# euroWS2811.net
KiCad netlist of a schematic drawn in EAGLE
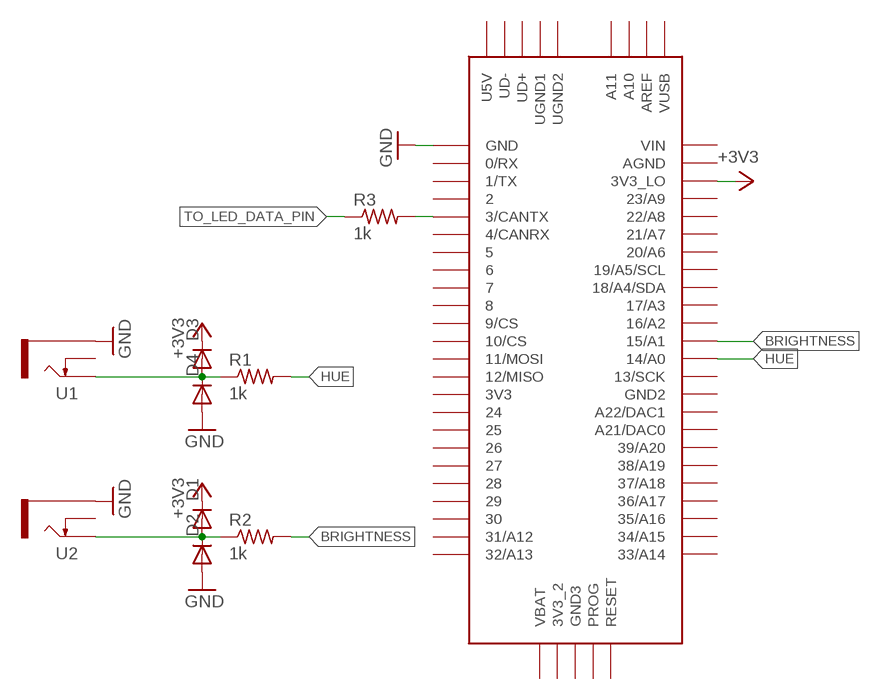
[diagram p0: schematic, sheet 1]

(export (version "E")
  (design (tool "Eeschema 10.0.6"))
  (components
    (comp (ref "D1")
      (value "SMALL_DIODEDO35-7")
      (footprint "eagle-import:DO35-7")
      (libsource (lib "eagle-import") (part "SMALL_DIODEDO35-7"))
    )
    (comp (ref "D2")
      (value "SMALL_DIODEDO35-7")
      (footprint "eagle-import:DO35-7")
      (libsource (lib "eagle-import") (part "SMALL_DIODEDO35-7"))
    )
    (comp (ref "D3")
      (value "SMALL_DIODEDO35-7")
      (footprint "eagle-import:DO35-7")
      (libsource (lib "eagle-import") (part "SMALL_DIODEDO35-7"))
    )
    (comp (ref "D4")
      (value "SMALL_DIODEDO35-7")
      (footprint "eagle-import:DO35-7")
      (libsource (lib "eagle-import") (part "SMALL_DIODEDO35-7"))
    )
    (comp (ref "R1")
      (value "1k")
      (footprint "eagle-import:0207_10")
      (libsource (lib "eagle-import") (part "R-US_0207/10"))
    )
    (comp (ref "R2")
      (value "1k")
      (footprint "eagle-import:0207_10")
      (libsource (lib "eagle-import") (part "R-US_0207/10"))
    )
    (comp (ref "R3")
      (value "1k")
      (footprint "eagle-import:0207_10")
      (libsource (lib "eagle-import") (part "R-US_0207/10"))
    )
    (comp (ref "U$1")
      (value "TEENSY_3.5/3.6")
      (footprint "eagle-import:TEENSY_3.5_3.6")
      (libsource (lib "eagle-import") (part "TEENSY_3.5/3.6"))
    )
    (comp (ref "U1")
      (value "THONKICONNNEW")
      (footprint "eagle-import:WQP-PJ301M-12_JACK")
      (libsource (lib "eagle-import") (part "THONKICONNNEW"))
    )
    (comp (ref "U2")
      (value "THONKICONNNEW")
      (footprint "eagle-import:WQP-PJ301M-12_JACK")
      (libsource (lib "eagle-import") (part "THONKICONNNEW"))
    )
  )
  (nets
    (net (code "1") (name "+3V3") (class "Default")
      (node (ref "D1") (pin "C") (pinfunction "C_C") (pintype "passive"))
      (node (ref "D3") (pin "C") (pinfunction "C_C") (pintype "passive"))
      (node (ref "U$1") (pin "3V3_LO") (pinfunction "3V3_LO_3V3_LO") (pintype "bidirectional"))
    )
    (net (code "2") (name "BRIGHTNESS") (class "Default")
      (node (ref "R2") (pin "2") (pinfunction "2_2") (pintype "passive"))
      (node (ref "U$1") (pin "15/A1") (pinfunction "15/A1_15/A1") (pintype "bidirectional"))
    )
    (net (code "3") (name "GND") (class "Default")
      (node (ref "D2") (pin "A") (pinfunction "A_A") (pintype "passive"))
      (node (ref "D4") (pin "A") (pinfunction "A_A") (pintype "passive"))
      (node (ref "U$1") (pin "GND") (pinfunction "GND_GND") (pintype "bidirectional"))
      (node (ref "U1") (pin "P$3_SLEEVE") (pinfunction "SLEEVE_P$3_SLEEVE") (pintype "passive"))
      (node (ref "U2") (pin "P$3_SLEEVE") (pinfunction "SLEEVE_P$3_SLEEVE") (pintype "passive"))
    )
    (net (code "4") (name "HUE") (class "Default")
      (node (ref "R1") (pin "2") (pinfunction "2_2") (pintype "passive"))
      (node (ref "U$1") (pin "14/A0") (pinfunction "14/A0_14/A0") (pintype "bidirectional"))
    )
    (net (code "5") (name "Net-(R3-Pad2)") (class "Default")
      (node (ref "R3") (pin "2") (pinfunction "2_2") (pintype "passive"))
      (node (ref "U$1") (pin "3/CANTX") (pinfunction "3/CANTX_3/CANTX") (pintype "bidirectional"))
    )
    (net (code "6") (name "Net-(U1-TIP)") (class "Default")
      (node (ref "D3") (pin "A") (pinfunction "A_A") (pintype "passive"))
      (node (ref "D4") (pin "C") (pinfunction "C_C") (pintype "passive"))
      (node (ref "R1") (pin "1") (pinfunction "1_1") (pintype "passive"))
      (node (ref "U1") (pin "P$1_TIP") (pinfunction "TIP_P$1_TIP") (pintype "passive"))
    )
    (net (code "7") (name "Net-(U2-TIP)") (class "Default")
      (node (ref "D1") (pin "A") (pinfunction "A_A") (pintype "passive"))
      (node (ref "D2") (pin "C") (pinfunction "C_C") (pintype "passive"))
      (node (ref "R2") (pin "1") (pinfunction "1_1") (pintype "passive"))
      (node (ref "U2") (pin "P$1_TIP") (pinfunction "TIP_P$1_TIP") (pintype "passive"))
    )
    (net (code "8") (name "TO_LED_DATA_PIN") (class "Default")
      (node (ref "R3") (pin "1") (pinfunction "1_1") (pintype "passive"))
    )
    (net (code "9") (name "unconnected-(U$1-A21{slash}DAC0-Pad21{slash}DAC0)") (class "Default")
      (node (ref "U$1") (pin "21/DAC0") (pinfunction "A21/DAC0_21/DAC0") (pintype "bidirectional"))
    )
    (net (code "10") (name "unconnected-(U$1-Pad0{slash}RX)") (class "Default")
      (node (ref "U$1") (pin "0/RX") (pinfunction "0/RX_0/RX") (pintype "bidirectional"))
    )
    (net (code "11") (name "unconnected-(U$1-Pad1{slash}TX)") (class "Default")
      (node (ref "U$1") (pin "1/TX") (pinfunction "1/TX_1/TX") (pintype "bidirectional"))
    )
    (net (code "12") (name "unconnected-(U$1-Pad2)") (class "Default")
      (node (ref "U$1") (pin "2") (pinfunction "2_2") (pintype "bidirectional"))
    )
    (net (code "13") (name "unconnected-(U$1-Pad3V3)") (class "Default")
      (node (ref "U$1") (pin "3V3") (pinfunction "3V3_3V3") (pintype "bidirectional"))
    )
    (net (code "14") (name "unconnected-(U$1-Pad3V3_2)") (class "Default")
      (node (ref "U$1") (pin "3V3_2") (pinfunction "3V3_2_3V3_2") (pintype "bidirectional"))
    )
    (net (code "15") (name "unconnected-(U$1-Pad4{slash}CANRX)") (class "Default")
      (node (ref "U$1") (pin "4/CANRX") (pinfunction "4/CANRX_4/CANRX") (pintype "bidirectional"))
    )
    (net (code "16") (name "unconnected-(U$1-Pad5)") (class "Default")
      (node (ref "U$1") (pin "5") (pinfunction "5_5") (pintype "bidirectional"))
    )
    (net (code "17") (name "unconnected-(U$1-Pad6)") (class "Default")
      (node (ref "U$1") (pin "6") (pinfunction "6_6") (pintype "bidirectional"))
    )
    (net (code "18") (name "unconnected-(U$1-Pad7)") (class "Default")
      (node (ref "U$1") (pin "7") (pinfunction "7_7") (pintype "bidirectional"))
    )
    (net (code "19") (name "unconnected-(U$1-Pad8)") (class "Default")
      (node (ref "U$1") (pin "8") (pinfunction "8_8") (pintype "bidirectional"))
    )
    (net (code "20") (name "unconnected-(U$1-Pad9{slash}CS)") (class "Default")
      (node (ref "U$1") (pin "9/CS") (pinfunction "9/CS_9/CS") (pintype "bidirectional"))
    )
    (net (code "21") (name "unconnected-(U$1-Pad10{slash}CS)") (class "Default")
      (node (ref "U$1") (pin "10/CS") (pinfunction "10/CS_10/CS") (pintype "bidirectional"))
    )
    (net (code "22") (name "unconnected-(U$1-Pad11{slash}MOSI)") (class "Default")
      (node (ref "U$1") (pin "11/MOSI") (pinfunction "11/MOSI_11/MOSI") (pintype "bidirectional"))
    )
    (net (code "23") (name "unconnected-(U$1-Pad12{slash}MISO)") (class "Default")
      (node (ref "U$1") (pin "12/MISO") (pinfunction "12/MISO_12/MISO") (pintype "bidirectional"))
    )
    (net (code "24") (name "unconnected-(U$1-Pad13{slash}SCK)") (class "Default")
      (node (ref "U$1") (pin "13/SCK") (pinfunction "13/SCK_13/SCK") (pintype "bidirectional"))
    )
    (net (code "25") (name "unconnected-(U$1-Pad16{slash}A2)") (class "Default")
      (node (ref "U$1") (pin "16/A2") (pinfunction "16/A2_16/A2") (pintype "bidirectional"))
    )
    (net (code "26") (name "unconnected-(U$1-Pad17{slash}A3)") (class "Default")
      (node (ref "U$1") (pin "17/A3") (pinfunction "17/A3_17/A3") (pintype "bidirectional"))
    )
    (net (code "27") (name "unconnected-(U$1-Pad18{slash}A4{slash}SDA)") (class "Default")
      (node (ref "U$1") (pin "18/A4/SDA") (pinfunction "18/A4/SDA_18/A4/SDA") (pintype "bidirectional"))
    )
    (net (code "28") (name "unconnected-(U$1-Pad19{slash}A5{slash}SCL)") (class "Default")
      (node (ref "U$1") (pin "19/A5/SCL") (pinfunction "19/A5/SCL_19/A5/SCL") (pintype "bidirectional"))
    )
    (net (code "29") (name "unconnected-(U$1-Pad20{slash}A6)") (class "Default")
      (node (ref "U$1") (pin "20/A6") (pinfunction "20/A6_20/A6") (pintype "bidirectional"))
    )
    (net (code "30") (name "unconnected-(U$1-Pad21{slash}A7)") (class "Default")
      (node (ref "U$1") (pin "21/A7") (pinfunction "21/A7_21/A7") (pintype "bidirectional"))
    )
    (net (code "31") (name "unconnected-(U$1-Pad22{slash}A8)") (class "Default")
      (node (ref "U$1") (pin "22/A8") (pinfunction "22/A8_22/A8") (pintype "bidirectional"))
    )
    (net (code "32") (name "unconnected-(U$1-Pad23{slash}A9)") (class "Default")
      (node (ref "U$1") (pin "23/A9") (pinfunction "23/A9_23/A9") (pintype "bidirectional"))
    )
    (net (code "33") (name "unconnected-(U$1-Pad24)") (class "Default")
      (node (ref "U$1") (pin "24") (pinfunction "24_24") (pintype "bidirectional"))
    )
    (net (code "34") (name "unconnected-(U$1-Pad25)") (class "Default")
      (node (ref "U$1") (pin "25") (pinfunction "25_25") (pintype "bidirectional"))
    )
    (net (code "35") (name "unconnected-(U$1-Pad26)") (class "Default")
      (node (ref "U$1") (pin "26") (pinfunction "26_26") (pintype "bidirectional"))
    )
    (net (code "36") (name "unconnected-(U$1-Pad27)") (class "Default")
      (node (ref "U$1") (pin "27") (pinfunction "27_27") (pintype "bidirectional"))
    )
    (net (code "37") (name "unconnected-(U$1-Pad28)") (class "Default")
      (node (ref "U$1") (pin "28") (pinfunction "28_28") (pintype "bidirectional"))
    )
    (net (code "38") (name "unconnected-(U$1-Pad29)") (class "Default")
      (node (ref "U$1") (pin "29") (pinfunction "29_29") (pintype "bidirectional"))
    )
    (net (code "39") (name "unconnected-(U$1-Pad30)") (class "Default")
      (node (ref "U$1") (pin "30") (pinfunction "30_30") (pintype "bidirectional"))
    )
    (net (code "40") (name "unconnected-(U$1-Pad31{slash}A12)") (class "Default")
      (node (ref "U$1") (pin "31/A12") (pinfunction "31/A12_31/A12") (pintype "bidirectional"))
    )
    (net (code "41") (name "unconnected-(U$1-Pad32{slash}A13)") (class "Default")
      (node (ref "U$1") (pin "32/A13") (pinfunction "32/A13_32/A13") (pintype "bidirectional"))
    )
    (net (code "42") (name "unconnected-(U$1-Pad33{slash}A14)") (class "Default")
      (node (ref "U$1") (pin "33/A14") (pinfunction "33/A14_33/A14") (pintype "bidirectional"))
    )
    (net (code "43") (name "unconnected-(U$1-Pad34{slash}A15)") (class "Default")
      (node (ref "U$1") (pin "34/A15") (pinfunction "34/A15_34/A15") (pintype "bidirectional"))
    )
    (net (code "44") (name "unconnected-(U$1-Pad35{slash}A16)") (class "Default")
      (node (ref "U$1") (pin "35/A16") (pinfunction "35/A16_35/A16") (pintype "bidirectional"))
    )
    (net (code "45") (name "unconnected-(U$1-Pad36{slash}A17)") (class "Default")
      (node (ref "U$1") (pin "36/A17") (pinfunction "36/A17_36/A17") (pintype "bidirectional"))
    )
    (net (code "46") (name "unconnected-(U$1-Pad37{slash}A18)") (class "Default")
      (node (ref "U$1") (pin "37/A18") (pinfunction "37/A18_37/A18") (pintype "bidirectional"))
    )
    (net (code "47") (name "unconnected-(U$1-Pad38{slash}A19)") (class "Default")
      (node (ref "U$1") (pin "38/A19") (pinfunction "38/A19_38/A19") (pintype "bidirectional"))
    )
    (net (code "48") (name "unconnected-(U$1-Pad39{slash}A20)") (class "Default")
      (node (ref "U$1") (pin "39/A20") (pinfunction "39/A20_39/A20") (pintype "bidirectional"))
    )
    (net (code "49") (name "unconnected-(U$1-PadA10)") (class "Default")
      (node (ref "U$1") (pin "A10") (pinfunction "A10_A10") (pintype "bidirectional"))
    )
    (net (code "50") (name "unconnected-(U$1-PadA11)") (class "Default")
      (node (ref "U$1") (pin "A11") (pinfunction "A11_A11") (pintype "bidirectional"))
    )
    (net (code "51") (name "unconnected-(U$1-PadA22{slash}DAC1)") (class "Default")
      (node (ref "U$1") (pin "A22/DAC1") (pinfunction "A22/DAC1_A22/DAC1") (pintype "bidirectional"))
    )
    (net (code "52") (name "unconnected-(U$1-PadAGND)") (class "Default")
      (node (ref "U$1") (pin "AGND") (pinfunction "AGND_AGND") (pintype "bidirectional"))
    )
    (net (code "53") (name "unconnected-(U$1-PadAREF)") (class "Default")
      (node (ref "U$1") (pin "AREF") (pinfunction "AREF_AREF") (pintype "bidirectional"))
    )
    (net (code "54") (name "unconnected-(U$1-PadGND2)") (class "Default")
      (node (ref "U$1") (pin "GND2") (pinfunction "GND2_GND2") (pintype "bidirectional"))
    )
    (net (code "55") (name "unconnected-(U$1-PadGND3)") (class "Default")
      (node (ref "U$1") (pin "GND3") (pinfunction "GND3_GND3") (pintype "bidirectional"))
    )
    (net (code "56") (name "unconnected-(U$1-PadPROG)") (class "Default")
      (node (ref "U$1") (pin "PROG") (pinfunction "PROG_PROG") (pintype "bidirectional"))
    )
    (net (code "57") (name "unconnected-(U$1-PadRESET)") (class "Default")
      (node (ref "U$1") (pin "RESET") (pinfunction "RESET_RESET") (pintype "bidirectional"))
    )
    (net (code "58") (name "unconnected-(U$1-PadU5V)") (class "Default")
      (node (ref "U$1") (pin "U5V") (pinfunction "U5V_U5V") (pintype "bidirectional"))
    )
    (net (code "59") (name "unconnected-(U$1-PadUD+)") (class "Default")
      (node (ref "U$1") (pin "UD+") (pinfunction "UD+_UD+") (pintype "bidirectional"))
    )
    (net (code "60") (name "unconnected-(U$1-PadUD-)") (class "Default")
      (node (ref "U$1") (pin "UD-") (pinfunction "UD-_UD-") (pintype "bidirectional"))
    )
    (net (code "61") (name "unconnected-(U$1-PadUGND1)") (class "Default")
      (node (ref "U$1") (pin "UGND1") (pinfunction "UGND1_UGND1") (pintype "bidirectional"))
    )
    (net (code "62") (name "unconnected-(U$1-PadUGND2)") (class "Default")
      (node (ref "U$1") (pin "UGND2") (pinfunction "UGND2_UGND2") (pintype "bidirectional"))
    )
    (net (code "63") (name "unconnected-(U$1-PadVBAT)") (class "Default")
      (node (ref "U$1") (pin "VBAT") (pinfunction "VBAT_VBAT") (pintype "bidirectional"))
    )
    (net (code "64") (name "unconnected-(U$1-PadVIN)") (class "Default")
      (node (ref "U$1") (pin "VIN") (pinfunction "VIN_VIN") (pintype "bidirectional"))
    )
    (net (code "65") (name "unconnected-(U$1-PadVUSB)") (class "Default")
      (node (ref "U$1") (pin "VUSB") (pinfunction "VUSB_VUSB") (pintype "bidirectional"))
    )
    (net (code "66") (name "unconnected-(U1-SWITCH-PadP$2_SWITCH)") (class "Default")
      (node (ref "U1") (pin "P$2_SWITCH") (pinfunction "SWITCH_P$2_SWITCH") (pintype "passive"))
    )
    (net (code "67") (name "unconnected-(U2-SWITCH-PadP$2_SWITCH)") (class "Default")
      (node (ref "U2") (pin "P$2_SWITCH") (pinfunction "SWITCH_P$2_SWITCH") (pintype "passive"))
    )
  )
)
